# up_down_buttons.net
KiCad netlist of a schematic drawn in EAGLE
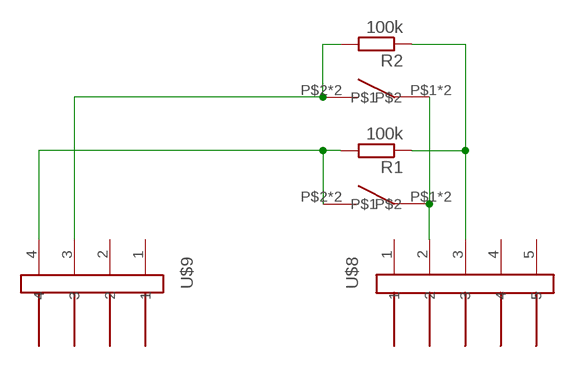
[diagram p0: schematic, sheet 1]

(export (version "E")
  (design (tool "Eeschema 10.0.6"))
  (components
    (comp (ref "R1")
      (value "100k")
      (footprint "eagle-import:R0603")
      (libsource (lib "eagle-import") (part "R-EU_R0603"))
    )
    (comp (ref "R2")
      (value "100k")
      (footprint "eagle-import:R0603")
      (libsource (lib "eagle-import") (part "R-EU_R0603"))
    )
    (comp (ref "U$1")
      (value "BUTTON_6.3X6.3")
      (footprint "eagle-import:BUTTON_6.2X6.2")
      (libsource (lib "eagle-import") (part "BUTTON_6.3X6.3"))
    )
    (comp (ref "U$2")
      (value "BUTTON_6.3X6.3")
      (footprint "eagle-import:BUTTON_6.2X6.2")
      (libsource (lib "eagle-import") (part "BUTTON_6.3X6.3"))
    )
    (comp (ref "U$8")
      (value "JUMPER5M")
      (footprint "eagle-import:JUMPER5M")
      (libsource (lib "eagle-import") (part "JUMPER5M"))
    )
    (comp (ref "U$9")
      (value "JUMPER4M")
      (footprint "eagle-import:JUMPER4M")
      (libsource (lib "eagle-import") (part "JUMPER4M"))
    )
  )
  (nets
    (net (code "1") (name "Net-(R1-Pad1)") (class "Default")
      (node (ref "R1") (pin "1") (pinfunction "1_1") (pintype "passive"))
      (node (ref "R2") (pin "1") (pinfunction "1_1") (pintype "passive"))
      (node (ref "U$8") (pin "3") (pinfunction "3_3") (pintype "bidirectional"))
    )
    (net (code "2") (name "Net-(R1-Pad2)") (class "Default")
      (node (ref "R1") (pin "2") (pinfunction "2_2") (pintype "passive"))
      (node (ref "U$1") (pin "P$2") (pinfunction "P$2_P$2") (pintype "bidirectional"))
      (node (ref "U$1") (pin "P$4") (pinfunction "P$2_P$4") (pintype "bidirectional"))
      (node (ref "U$9") (pin "4") (pinfunction "4_4") (pintype "bidirectional"))
    )
    (net (code "3") (name "Net-(R2-Pad2)") (class "Default")
      (node (ref "R2") (pin "2") (pinfunction "2_2") (pintype "passive"))
      (node (ref "U$2") (pin "P$2") (pinfunction "P$2_P$2") (pintype "bidirectional"))
      (node (ref "U$2") (pin "P$4") (pinfunction "P$2_P$4") (pintype "bidirectional"))
      (node (ref "U$9") (pin "3") (pinfunction "3_3") (pintype "bidirectional"))
    )
    (net (code "4") (name "Net-(U$1-P$1-PadP$3)") (class "Default")
      (node (ref "U$1") (pin "P$1") (pinfunction "P$1_P$1") (pintype "bidirectional"))
      (node (ref "U$1") (pin "P$3") (pinfunction "P$1_P$3") (pintype "bidirectional"))
      (node (ref "U$2") (pin "P$1") (pinfunction "P$1_P$1") (pintype "bidirectional"))
      (node (ref "U$2") (pin "P$3") (pinfunction "P$1_P$3") (pintype "bidirectional"))
      (node (ref "U$8") (pin "2") (pinfunction "2_2") (pintype "bidirectional"))
    )
    (net (code "5") (name "unconnected-(U$8-Pad1)") (class "Default")
      (node (ref "U$8") (pin "1") (pinfunction "1_1") (pintype "bidirectional"))
    )
    (net (code "6") (name "unconnected-(U$8-Pad4)") (class "Default")
      (node (ref "U$8") (pin "4") (pinfunction "4_4") (pintype "bidirectional"))
    )
    (net (code "7") (name "unconnected-(U$8-Pad5)") (class "Default")
      (node (ref "U$8") (pin "5") (pinfunction "5_5") (pintype "bidirectional"))
    )
    (net (code "8") (name "unconnected-(U$9-Pad1)") (class "Default")
      (node (ref "U$9") (pin "1") (pinfunction "1_1") (pintype "bidirectional"))
    )
    (net (code "9") (name "unconnected-(U$9-Pad2)") (class "Default")
      (node (ref "U$9") (pin "2") (pinfunction "2_2") (pintype "bidirectional"))
    )
  )
)
